# Translators_AWG.net
KiCad netlist of a schematic drawn in Altium Designer
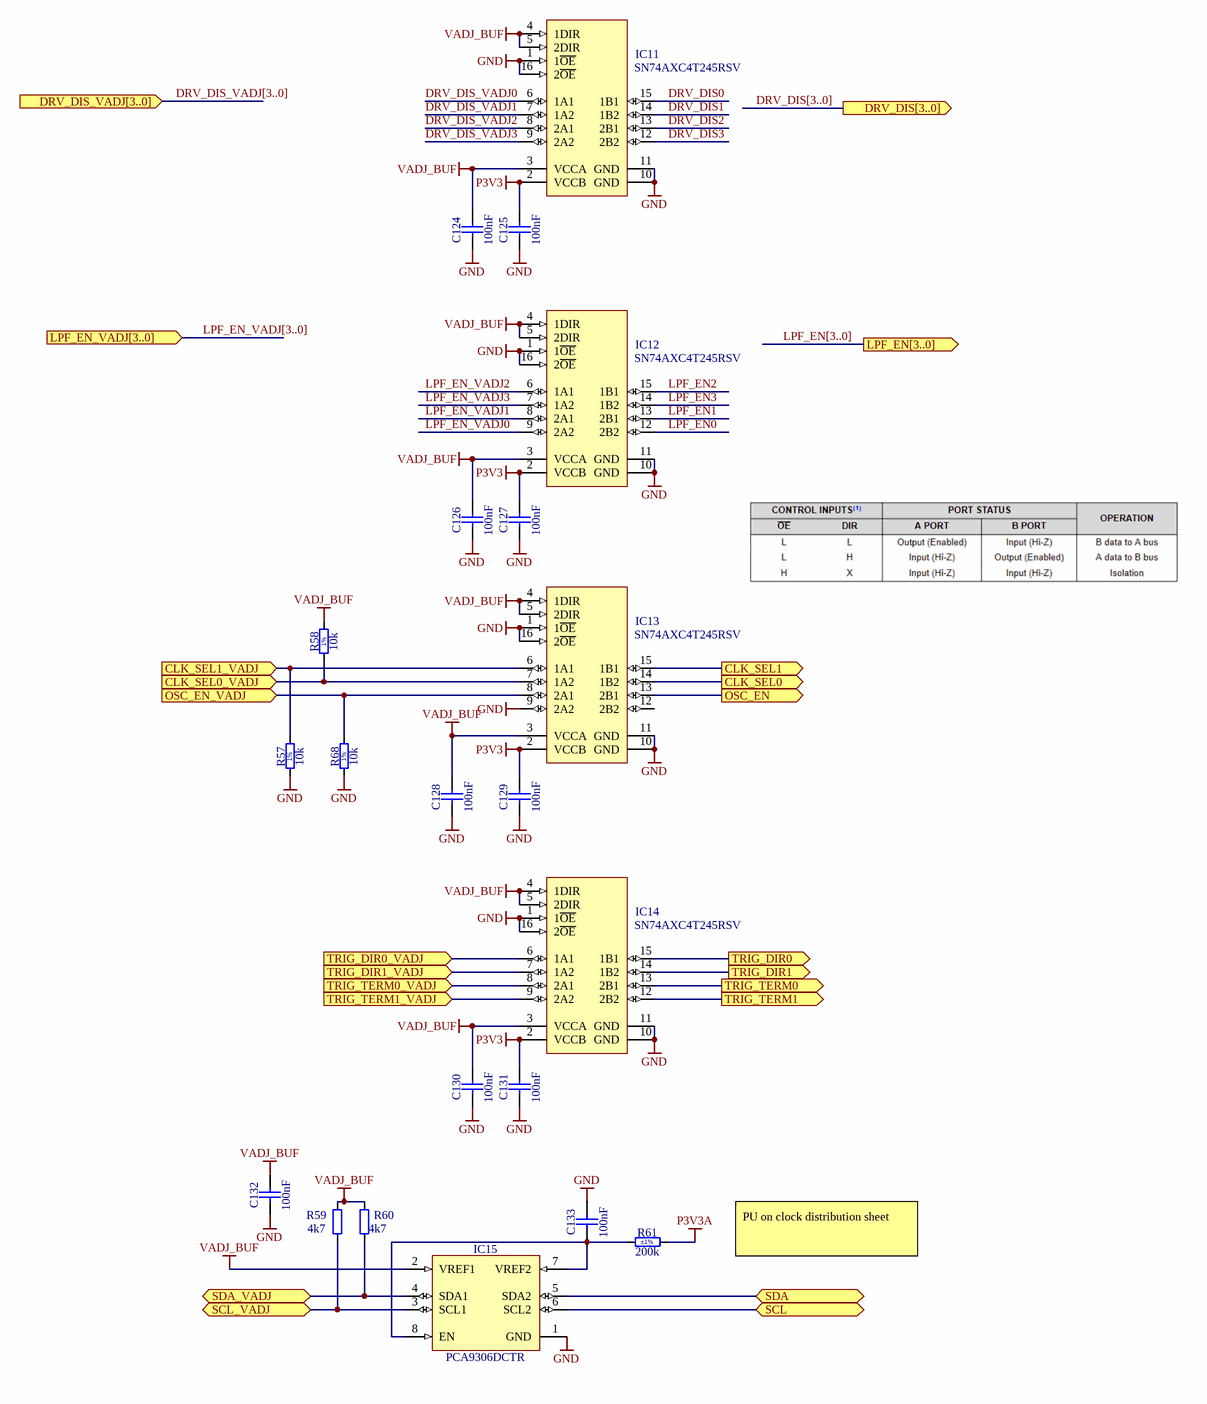
[diagram p0: Translators_AWG.SchDoc]

(export (version "E")
  (design (tool "Eeschema 10.0.6"))
  (components
    (comp (ref "C124")
      (value "100nF")
      (footprint "CAPC1005X55N")
      (description "Non-polarised capacitor")
      (fields
        (field (name "PART NUMBER") "CC0402_100NF_16V_10%_X7R")
        (field (name "VOLTAGE") "16V")
        (field (name "AUTHOR") "CERN DEM JLC")
      )
      (libsource (lib "Capacitors") (part "Capacitor - non polarized"))
    )
    (comp (ref "C125")
      (value "100nF")
      (footprint "CAPC1005X55N")
      (description "Non-polarised capacitor")
      (fields
        (field (name "PART NUMBER") "CC0402_100NF_16V_10%_X7R")
        (field (name "VOLTAGE") "16V")
        (field (name "AUTHOR") "CERN DEM JLC")
      )
      (libsource (lib "Capacitors") (part "Capacitor - non polarized"))
    )
    (comp (ref "C126")
      (value "100nF")
      (footprint "CAPC1005X55N")
      (description "Non-polarised capacitor")
      (fields
        (field (name "PART NUMBER") "CC0402_100NF_16V_10%_X7R")
        (field (name "VOLTAGE") "16V")
        (field (name "AUTHOR") "CERN DEM JLC")
      )
      (libsource (lib "Capacitors") (part "Capacitor - non polarized"))
    )
    (comp (ref "C127")
      (value "100nF")
      (footprint "CAPC1005X55N")
      (description "Non-polarised capacitor")
      (fields
        (field (name "PART NUMBER") "CC0402_100NF_16V_10%_X7R")
        (field (name "VOLTAGE") "16V")
        (field (name "AUTHOR") "CERN DEM JLC")
      )
      (libsource (lib "Capacitors") (part "Capacitor - non polarized"))
    )
    (comp (ref "C128")
      (value "100nF")
      (footprint "CAPC1005X55N")
      (description "Non-polarised capacitor")
      (fields
        (field (name "PART NUMBER") "CC0402_100NF_16V_10%_X7R")
        (field (name "VOLTAGE") "16V")
        (field (name "AUTHOR") "CERN DEM JLC")
      )
      (libsource (lib "Capacitors") (part "Capacitor - non polarized"))
    )
    (comp (ref "C129")
      (value "100nF")
      (footprint "CAPC1005X55N")
      (description "Non-polarised capacitor")
      (fields
        (field (name "PART NUMBER") "CC0402_100NF_16V_10%_X7R")
        (field (name "VOLTAGE") "16V")
        (field (name "AUTHOR") "CERN DEM JLC")
      )
      (libsource (lib "Capacitors") (part "Capacitor - non polarized"))
    )
    (comp (ref "C130")
      (value "100nF")
      (footprint "CAPC1005X55N")
      (description "Non-polarised capacitor")
      (fields
        (field (name "PART NUMBER") "CC0402_100NF_16V_10%_X7R")
        (field (name "VOLTAGE") "16V")
        (field (name "AUTHOR") "CERN DEM JLC")
      )
      (libsource (lib "Capacitors") (part "Capacitor - non polarized"))
    )
    (comp (ref "C131")
      (value "100nF")
      (footprint "CAPC1005X55N")
      (description "Non-polarised capacitor")
      (fields
        (field (name "PART NUMBER") "CC0402_100NF_16V_10%_X7R")
        (field (name "VOLTAGE") "16V")
        (field (name "AUTHOR") "CERN DEM JLC")
      )
      (libsource (lib "Capacitors") (part "Capacitor - non polarized"))
    )
    (comp (ref "C132")
      (value "100nF")
      (footprint "CAPC1005X55N")
      (description "Non-polarised capacitor")
      (fields
        (field (name "PART NUMBER") "CC0402_100NF_16V_10%_X7R")
        (field (name "VOLTAGE") "16V")
        (field (name "AUTHOR") "CERN DEM JLC")
      )
      (libsource (lib "Capacitors") (part "Capacitor - non polarized"))
    )
    (comp (ref "C133")
      (value "100nF")
      (footprint "CAPC1005X55N")
      (description "Non-polarised capacitor")
      (fields
        (field (name "PART NUMBER") "CC0402_100NF_16V_10%_X7R")
        (field (name "VOLTAGE") "16V")
        (field (name "AUTHOR") "CERN DEM JLC")
      )
      (libsource (lib "Capacitors") (part "Capacitor - non polarized"))
    )
    (comp (ref "IC11")
      (value "SN74AXC4T245RSV")
      (footprint "QFN40P180X260X55-16N")
      (description "4-Bit Dual-Supply Bus Transceiver with Configurable Voltage Translation and 3-State Output")
      (fields (field (name "MANUFACTURER") "TEXAS INSTRUMENTS") (field (name "AUTHOR") "GK"))
      (libsource (lib "ICS-logic") (part "SN74AXC4T245"))
    )
    (comp (ref "IC12")
      (value "SN74AXC4T245RSV")
      (footprint "QFN40P180X260X55-16N")
      (description "4-Bit Dual-Supply Bus Transceiver with Configurable Voltage Translation and 3-State Output")
      (fields (field (name "MANUFACTURER") "TEXAS INSTRUMENTS") (field (name "AUTHOR") "GK"))
      (libsource (lib "ICS-logic") (part "SN74AXC4T245"))
    )
    (comp (ref "IC13")
      (value "SN74AXC4T245RSV")
      (footprint "QFN40P180X260X55-16N")
      (description "4-Bit Dual-Supply Bus Transceiver with Configurable Voltage Translation and 3-State Output")
      (fields (field (name "MANUFACTURER") "TEXAS INSTRUMENTS") (field (name "AUTHOR") "GK"))
      (libsource (lib "ICS-logic") (part "SN74AXC4T245"))
    )
    (comp (ref "IC14")
      (value "SN74AXC4T245RSV")
      (footprint "QFN40P180X260X55-16N")
      (description "4-Bit Dual-Supply Bus Transceiver with Configurable Voltage Translation and 3-State Output")
      (fields (field (name "MANUFACTURER") "TEXAS INSTRUMENTS") (field (name "AUTHOR") "GK"))
      (libsource (lib "ICS-logic") (part "SN74AXC4T245"))
    )
    (comp (ref "IC15")
      (value "PCA9306DCTR")
      (footprint "SOP65P400X130-8N")
      (description "Dual Bidirectional I2C Bus And SMBus Voltage-Level Translator")
      (fields (field (name "MANUFACTURER") "TEXAS INSTRUMENTS") (field (name "AUTHOR") "CERN DEM JLC"))
      (libsource (lib "ICs And Semiconductors") (part "PCA9306DC"))
    )
    (comp (ref "R57")
      (value "10k")
      (footprint "RESC1005X40N")
      (description "Resistor - 1%")
      (fields
        (field (name "PART NUMBER") "R0402_10K_1%_0.0625W_100PPM")
        (field (name "POWER") "0.0625W")
        (field (name "AUTHOR") "CERN DEM JLC")
      )
      (libsource (lib "Resistors") (part "Resistor - 1%"))
    )
    (comp (ref "R58")
      (value "10k")
      (footprint "RESC1005X40N")
      (description "Resistor - 1%")
      (fields
        (field (name "PART NUMBER") "R0402_10K_1%_0.0625W_100PPM")
        (field (name "POWER") "0.0625W")
        (field (name "AUTHOR") "CERN DEM JLC")
      )
      (libsource (lib "Resistors") (part "Resistor - 1%"))
    )
    (comp (ref "R59")
      (value "4k7")
      (footprint "RESC1005X40N")
      (description "Resistor - 1%")
      (fields
        (field (name "PART NUMBER") "R0402_4K7_1%_0.0625W_100PPM")
        (field (name "POWER") "0.0625W")
        (field (name "AUTHOR") "CERN DEM JLC")
      )
      (libsource (lib "Resistors") (part "Resistor - 1%"))
    )
    (comp (ref "R60")
      (value "4k7")
      (footprint "RESC1005X40N")
      (description "Resistor - 1%")
      (fields
        (field (name "PART NUMBER") "R0402_4K7_1%_0.0625W_100PPM")
        (field (name "POWER") "0.0625W")
        (field (name "AUTHOR") "CERN DEM JLC")
      )
      (libsource (lib "Resistors") (part "Resistor - 1%"))
    )
    (comp (ref "R61")
      (value "200k")
      (footprint "RESC1005X40N")
      (description "Resistor - 1%")
      (fields
        (field (name "TOLERANCE") "±1%")
        (field (name "PART NUMBER") "R0402_200K_1%_0.0625W_100PPM")
        (field (name "POWER") "0.0625W")
        (field (name "AUTHOR") "CERN DEM JLC")
      )
      (libsource (lib "Resistors") (part "Resistor - 1%"))
    )
    (comp (ref "R68")
      (value "10k")
      (footprint "RESC1005X40N")
      (description "Resistor - 1%")
      (fields
        (field (name "PART NUMBER") "R0402_10K_1%_0.0625W_100PPM")
        (field (name "POWER") "0.0625W")
        (field (name "AUTHOR") "CERN DEM JLC")
      )
      (libsource (lib "Resistors") (part "Resistor - 1%"))
    )
  )
  (nets
    (net (code "1") (name "/CLK_SEL0") (class "Default")
      (node (ref "IC13") (pin "14") (pinfunction "1B2_14") (pintype "bidirectional"))
    )
    (net (code "2") (name "/CLK_SEL0_VADJ") (class "Default")
      (node (ref "IC13") (pin "7") (pinfunction "1A2_7") (pintype "bidirectional"))
      (node (ref "R58") (pin "1") (pinfunction "1_1") (pintype "passive"))
    )
    (net (code "3") (name "/CLK_SEL1") (class "Default")
      (node (ref "IC13") (pin "15") (pinfunction "1B1_15") (pintype "bidirectional"))
    )
    (net (code "4") (name "/CLK_SEL1_VADJ") (class "Default")
      (node (ref "IC13") (pin "6") (pinfunction "1A1_6") (pintype "bidirectional"))
      (node (ref "R57") (pin "2") (pinfunction "2_2") (pintype "passive"))
    )
    (net (code "5") (name "/DRV_DIS0") (class "Default")
      (node (ref "IC11") (pin "15") (pinfunction "1B1_15") (pintype "bidirectional"))
    )
    (net (code "6") (name "/DRV_DIS1") (class "Default")
      (node (ref "IC11") (pin "14") (pinfunction "1B2_14") (pintype "bidirectional"))
    )
    (net (code "7") (name "/DRV_DIS2") (class "Default")
      (node (ref "IC11") (pin "13") (pinfunction "2B1_13") (pintype "bidirectional"))
    )
    (net (code "8") (name "/DRV_DIS3") (class "Default")
      (node (ref "IC11") (pin "12") (pinfunction "2B2_12") (pintype "bidirectional"))
    )
    (net (code "10") (name "/DRV_DIS_VADJ0") (class "Default")
      (node (ref "IC11") (pin "6") (pinfunction "1A1_6") (pintype "bidirectional"))
    )
    (net (code "11") (name "/DRV_DIS_VADJ1") (class "Default")
      (node (ref "IC11") (pin "7") (pinfunction "1A2_7") (pintype "bidirectional"))
    )
    (net (code "12") (name "/DRV_DIS_VADJ2") (class "Default")
      (node (ref "IC11") (pin "8") (pinfunction "2A1_8") (pintype "bidirectional"))
    )
    (net (code "13") (name "/DRV_DIS_VADJ3") (class "Default")
      (node (ref "IC11") (pin "9") (pinfunction "2A2_9") (pintype "bidirectional"))
    )
    (net (code "15") (name "/LPF_EN0") (class "Default")
      (node (ref "IC12") (pin "12") (pinfunction "2B2_12") (pintype "bidirectional"))
    )
    (net (code "16") (name "/LPF_EN1") (class "Default")
      (node (ref "IC12") (pin "13") (pinfunction "2B1_13") (pintype "bidirectional"))
    )
    (net (code "17") (name "/LPF_EN2") (class "Default")
      (node (ref "IC12") (pin "15") (pinfunction "1B1_15") (pintype "bidirectional"))
    )
    (net (code "18") (name "/LPF_EN3") (class "Default")
      (node (ref "IC12") (pin "14") (pinfunction "1B2_14") (pintype "bidirectional"))
    )
    (net (code "20") (name "/LPF_EN_VADJ0") (class "Default")
      (node (ref "IC12") (pin "9") (pinfunction "2A2_9") (pintype "bidirectional"))
    )
    (net (code "21") (name "/LPF_EN_VADJ1") (class "Default")
      (node (ref "IC12") (pin "8") (pinfunction "2A1_8") (pintype "bidirectional"))
    )
    (net (code "22") (name "/LPF_EN_VADJ2") (class "Default")
      (node (ref "IC12") (pin "6") (pinfunction "1A1_6") (pintype "bidirectional"))
    )
    (net (code "23") (name "/LPF_EN_VADJ3") (class "Default")
      (node (ref "IC12") (pin "7") (pinfunction "1A2_7") (pintype "bidirectional"))
    )
    (net (code "25") (name "/OSC_EN") (class "Default")
      (node (ref "IC13") (pin "13") (pinfunction "2B1_13") (pintype "bidirectional"))
    )
    (net (code "26") (name "/OSC_EN_VADJ") (class "Default")
      (node (ref "IC13") (pin "8") (pinfunction "2A1_8") (pintype "bidirectional"))
      (node (ref "R68") (pin "2") (pinfunction "2_2") (pintype "passive"))
    )
    (net (code "27") (name "/SCL") (class "Default")
      (node (ref "IC15") (pin "6") (pinfunction "SCL2_6") (pintype "bidirectional"))
    )
    (net (code "28") (name "/SCL_VADJ") (class "Default")
      (node (ref "IC15") (pin "3") (pinfunction "SCL1_3") (pintype "bidirectional"))
      (node (ref "R59") (pin "1") (pinfunction "1_1") (pintype "passive"))
    )
    (net (code "29") (name "/SDA") (class "Default")
      (node (ref "IC15") (pin "5") (pinfunction "SDA2_5") (pintype "bidirectional"))
    )
    (net (code "30") (name "/SDA_VADJ") (class "Default")
      (node (ref "IC15") (pin "4") (pinfunction "SDA1_4") (pintype "bidirectional"))
      (node (ref "R60") (pin "1") (pinfunction "1_1") (pintype "passive"))
    )
    (net (code "31") (name "/TRIG_DIR0") (class "Default")
      (node (ref "IC14") (pin "15") (pinfunction "1B1_15") (pintype "bidirectional"))
    )
    (net (code "32") (name "/TRIG_DIR0_VADJ") (class "Default")
      (node (ref "IC14") (pin "6") (pinfunction "1A1_6") (pintype "bidirectional"))
    )
    (net (code "33") (name "/TRIG_DIR1") (class "Default")
      (node (ref "IC14") (pin "14") (pinfunction "1B2_14") (pintype "bidirectional"))
    )
    (net (code "34") (name "/TRIG_DIR1_VADJ") (class "Default")
      (node (ref "IC14") (pin "7") (pinfunction "1A2_7") (pintype "bidirectional"))
    )
    (net (code "35") (name "/TRIG_TERM0") (class "Default")
      (node (ref "IC14") (pin "13") (pinfunction "2B1_13") (pintype "bidirectional"))
    )
    (net (code "36") (name "/TRIG_TERM0_VADJ") (class "Default")
      (node (ref "IC14") (pin "8") (pinfunction "2A1_8") (pintype "bidirectional"))
    )
    (net (code "37") (name "/TRIG_TERM1") (class "Default")
      (node (ref "IC14") (pin "12") (pinfunction "2B2_12") (pintype "bidirectional"))
    )
    (net (code "38") (name "/TRIG_TERM1_VADJ") (class "Default")
      (node (ref "IC14") (pin "9") (pinfunction "2A2_9") (pintype "bidirectional"))
    )
    (net (code "39") (name "GND") (class "Default")
      (node (ref "C124") (pin "1") (pinfunction "1_1") (pintype "passive"))
      (node (ref "C125") (pin "1") (pinfunction "1_1") (pintype "passive"))
      (node (ref "C126") (pin "1") (pinfunction "1_1") (pintype "passive"))
      (node (ref "C127") (pin "1") (pinfunction "1_1") (pintype "passive"))
      (node (ref "C128") (pin "1") (pinfunction "1_1") (pintype "passive"))
      (node (ref "C129") (pin "1") (pinfunction "1_1") (pintype "passive"))
      (node (ref "C130") (pin "1") (pinfunction "1_1") (pintype "passive"))
      (node (ref "C131") (pin "1") (pinfunction "1_1") (pintype "passive"))
      (node (ref "C132") (pin "1") (pinfunction "1_1") (pintype "passive"))
      (node (ref "C133") (pin "2") (pinfunction "2_2") (pintype "passive"))
      (node (ref "IC11") (pin "1") (pinfunction "1~{OE}_1") (pintype "input"))
      (node (ref "IC11") (pin "10") (pinfunction "GND_10") (pintype "power_in"))
      (node (ref "IC11") (pin "11") (pinfunction "GND_11") (pintype "power_in"))
      (node (ref "IC11") (pin "16") (pinfunction "2~{OE}_16") (pintype "input"))
      (node (ref "IC12") (pin "1") (pinfunction "1~{OE}_1") (pintype "input"))
      (node (ref "IC12") (pin "10") (pinfunction "GND_10") (pintype "power_in"))
      (node (ref "IC12") (pin "11") (pinfunction "GND_11") (pintype "power_in"))
      (node (ref "IC12") (pin "16") (pinfunction "2~{OE}_16") (pintype "input"))
      (node (ref "IC13") (pin "1") (pinfunction "1~{OE}_1") (pintype "input"))
      (node (ref "IC13") (pin "10") (pinfunction "GND_10") (pintype "power_in"))
      (node (ref "IC13") (pin "11") (pinfunction "GND_11") (pintype "power_in"))
      (node (ref "IC13") (pin "16") (pinfunction "2~{OE}_16") (pintype "input"))
      (node (ref "IC13") (pin "9") (pinfunction "2A2_9") (pintype "bidirectional"))
      (node (ref "IC14") (pin "1") (pinfunction "1~{OE}_1") (pintype "input"))
      (node (ref "IC14") (pin "10") (pinfunction "GND_10") (pintype "power_in"))
      (node (ref "IC14") (pin "11") (pinfunction "GND_11") (pintype "power_in"))
      (node (ref "IC14") (pin "16") (pinfunction "2~{OE}_16") (pintype "input"))
      (node (ref "IC15") (pin "1") (pinfunction "GND_1") (pintype "power_in"))
      (node (ref "R57") (pin "1") (pinfunction "1_1") (pintype "passive"))
      (node (ref "R68") (pin "1") (pinfunction "1_1") (pintype "passive"))
    )
    (net (code "40") (name "Net-(IC15-EN)") (class "Default")
      (node (ref "C133") (pin "1") (pinfunction "1_1") (pintype "passive"))
      (node (ref "IC15") (pin "7") (pinfunction "VREF2_7") (pintype "input"))
      (node (ref "IC15") (pin "8") (pinfunction "EN_8") (pintype "input"))
      (node (ref "R61") (pin "1") (pinfunction "1_1") (pintype "passive"))
    )
    (net (code "41") (name "P3V3") (class "Default")
      (node (ref "C125") (pin "2") (pinfunction "2_2") (pintype "passive"))
      (node (ref "C127") (pin "2") (pinfunction "2_2") (pintype "passive"))
      (node (ref "C129") (pin "2") (pinfunction "2_2") (pintype "passive"))
      (node (ref "C131") (pin "2") (pinfunction "2_2") (pintype "passive"))
      (node (ref "IC11") (pin "2") (pinfunction "VCCB_2") (pintype "power_in"))
      (node (ref "IC12") (pin "2") (pinfunction "VCCB_2") (pintype "power_in"))
      (node (ref "IC13") (pin "2") (pinfunction "VCCB_2") (pintype "power_in"))
      (node (ref "IC14") (pin "2") (pinfunction "VCCB_2") (pintype "power_in"))
    )
    (net (code "42") (name "P3V3A") (class "Default")
      (node (ref "R61") (pin "2") (pinfunction "2_2") (pintype "passive"))
    )
    (net (code "43") (name "VADJ_BUF") (class "Default")
      (node (ref "C124") (pin "2") (pinfunction "2_2") (pintype "passive"))
      (node (ref "C126") (pin "2") (pinfunction "2_2") (pintype "passive"))
      (node (ref "C128") (pin "2") (pinfunction "2_2") (pintype "passive"))
      (node (ref "C130") (pin "2") (pinfunction "2_2") (pintype "passive"))
      (node (ref "C132") (pin "2") (pinfunction "2_2") (pintype "passive"))
      (node (ref "IC11") (pin "3") (pinfunction "VCCA_3") (pintype "power_in"))
      (node (ref "IC11") (pin "4") (pinfunction "1DIR_4") (pintype "input"))
      (node (ref "IC11") (pin "5") (pinfunction "2DIR_5") (pintype "input"))
      (node (ref "IC12") (pin "3") (pinfunction "VCCA_3") (pintype "power_in"))
      (node (ref "IC12") (pin "4") (pinfunction "1DIR_4") (pintype "input"))
      (node (ref "IC12") (pin "5") (pinfunction "2DIR_5") (pintype "input"))
      (node (ref "IC13") (pin "3") (pinfunction "VCCA_3") (pintype "power_in"))
      (node (ref "IC13") (pin "4") (pinfunction "1DIR_4") (pintype "input"))
      (node (ref "IC13") (pin "5") (pinfunction "2DIR_5") (pintype "input"))
      (node (ref "IC14") (pin "3") (pinfunction "VCCA_3") (pintype "power_in"))
      (node (ref "IC14") (pin "4") (pinfunction "1DIR_4") (pintype "input"))
      (node (ref "IC14") (pin "5") (pinfunction "2DIR_5") (pintype "input"))
      (node (ref "IC15") (pin "2") (pinfunction "VREF1_2") (pintype "input"))
      (node (ref "R58") (pin "2") (pinfunction "2_2") (pintype "passive"))
      (node (ref "R59") (pin "2") (pinfunction "2_2") (pintype "passive"))
      (node (ref "R60") (pin "2") (pinfunction "2_2") (pintype "passive"))
    )
    (net (code "44") (name "unconnected-(IC13-2B2-Pad12)") (class "Default")
      (node (ref "IC13") (pin "12") (pinfunction "2B2_12") (pintype "bidirectional"))
    )
  )
)
